# couple-pointing.net
KiCad netlist of a schematic drawn in EasyEDA Pro
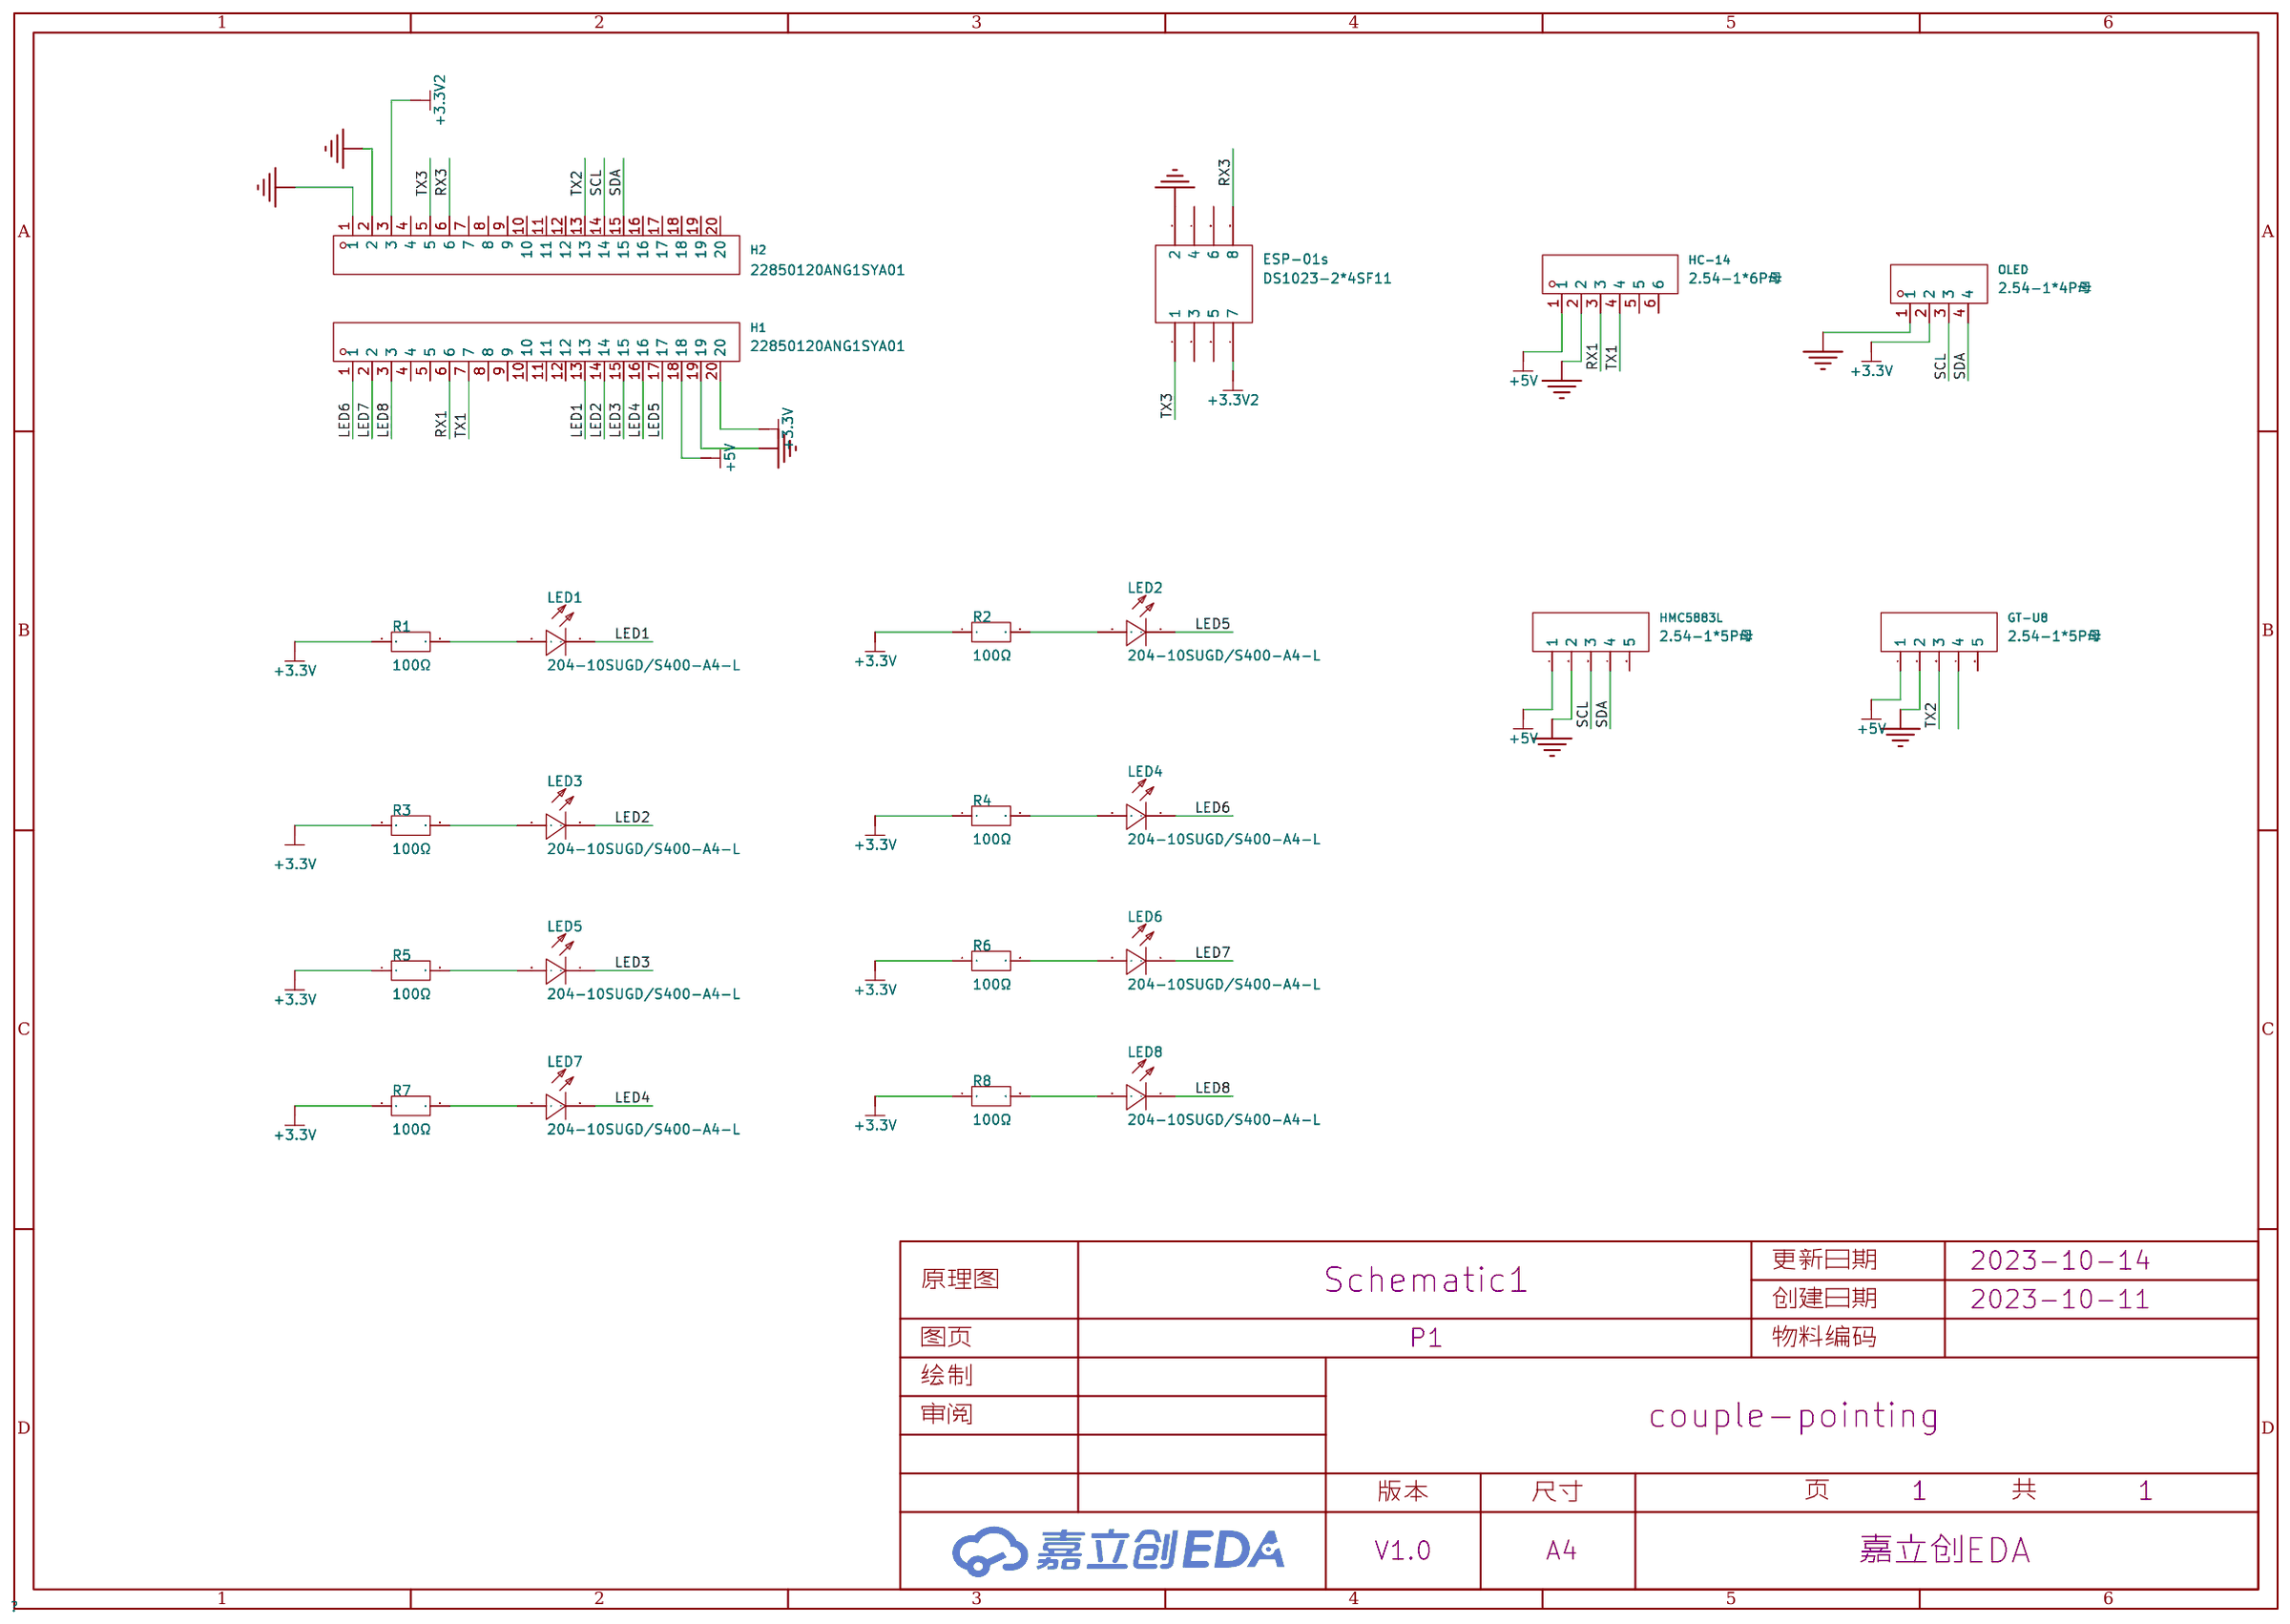
[diagram p0: schematic sheet]

(export (version "E")
  (design (tool "Eeschema 10.0.6"))
  (components
    (comp (ref "ESP-01s")
      (value "DS1023-2*4SF11")
      (footprint "easyedapro:HDR-TH_8P-P2.54-V-F-R2-C4-S2.54")
      (description "排数:双排;总孔位数:8P;间距:2.54mm;插孔结构:2x4P;行距:2.54mm;安装类型:直插;塑高:-;触头材质:-;触头镀层:-;")
      (fields (field (name "Manufacturer") "CONNFLY"))
      (libsource (lib "easyedapro") (part "DS1023-2*4SF11"))
    )
    (comp (ref "GT-U8")
      (value "2.54-1*5P母")
      (footprint "easyedapro:HDR-TH_5P-P2.54-V-F")
      (description "排数:单排;总孔位数:5P;间距:2.54mm;插孔结构:1x5P;行距:-;安装类型:直插;塑高:-;触头材质:-;触头镀层:-;")
      (fields (field (name "Manufacturer") "BOOMELE(博穆精密)"))
      (libsource (lib "easyedapro") (part "Header-Female-2.54_1x5"))
    )
    (comp (ref "H1")
      (value "22850120ANG1SYA01")
      (footprint "easyedapro:HDR-TH_20P-P2.54-V-F")
      (description "排数:单排;总孔位数:20P;间距:2.54mm;插孔结构:1x20P;行距:-;安装类型:直插;塑高:-;触头材质:黄铜;触头镀层:-;")
      (fields (field (name "Manufacturer") "JILN(锦凌)"))
      (libsource (lib "easyedapro") (part "22850120ANG1SYA01"))
    )
    (comp (ref "H2")
      (value "22850120ANG1SYA01")
      (footprint "easyedapro:HDR-TH_20P-P2.54-V-F")
      (description "排数:单排;总孔位数:20P;间距:2.54mm;插孔结构:1x20P;行距:-;安装类型:直插;塑高:-;触头材质:黄铜;触头镀层:-;")
      (fields (field (name "Manufacturer") "JILN(锦凌)"))
      (libsource (lib "easyedapro") (part "22850120ANG1SYA01"))
    )
    (comp (ref "HC-14")
      (value "2.54-1*6P母")
      (footprint "easyedapro:HDR-TH_6P-P2.54-V-F")
      (description "排数:单排;总孔位数:6P;间距:2.54mm;插孔结构:1x6P;行距:-;安装类型:直插;塑高:-;触头材质:-;触头镀层:-;")
      (fields (field (name "Manufacturer") "BOOMELE(博穆精密)"))
      (libsource (lib "easyedapro") (part "Header-Female-2.54_1x6"))
    )
    (comp (ref "HMC5883L")
      (value "2.54-1*5P母")
      (footprint "easyedapro:HDR-TH_5P-P2.54-V-F")
      (description "排数:单排;总孔位数:5P;间距:2.54mm;插孔结构:1x5P;行距:-;安装类型:直插;塑高:-;触头材质:-;触头镀层:-;")
      (fields (field (name "Manufacturer") "BOOMELE(博穆精密)"))
      (libsource (lib "easyedapro") (part "Header-Female-2.54_1x5"))
    )
    (comp (ref "LED1")
      (value "204-10SUGD/S400-A4-L")
      (footprint "easyedapro:LED-TH_BD3.9-P2.54-RD")
      (fields (field (name "Manufacturer") "EVERLIGHT(亿光)"))
      (libsource (lib "easyedapro") (part "204-10SUGD/S400-A4-L"))
    )
    (comp (ref "LED2")
      (value "204-10SUGD/S400-A4-L")
      (footprint "easyedapro:LED-TH_BD3.9-P2.54-RD")
      (fields (field (name "Manufacturer") "EVERLIGHT(亿光)"))
      (libsource (lib "easyedapro") (part "204-10SUGD/S400-A4-L"))
    )
    (comp (ref "LED3")
      (value "204-10SUGD/S400-A4-L")
      (footprint "easyedapro:LED-TH_BD3.9-P2.54-RD")
      (fields (field (name "Manufacturer") "EVERLIGHT(亿光)"))
      (libsource (lib "easyedapro") (part "204-10SUGD/S400-A4-L"))
    )
    (comp (ref "LED4")
      (value "204-10SUGD/S400-A4-L")
      (footprint "easyedapro:LED-TH_BD3.9-P2.54-RD")
      (fields (field (name "Manufacturer") "EVERLIGHT(亿光)"))
      (libsource (lib "easyedapro") (part "204-10SUGD/S400-A4-L"))
    )
    (comp (ref "LED5")
      (value "204-10SUGD/S400-A4-L")
      (footprint "easyedapro:LED-TH_BD3.9-P2.54-RD")
      (fields (field (name "Manufacturer") "EVERLIGHT(亿光)"))
      (libsource (lib "easyedapro") (part "204-10SUGD/S400-A4-L"))
    )
    (comp (ref "LED6")
      (value "204-10SUGD/S400-A4-L")
      (footprint "easyedapro:LED-TH_BD3.9-P2.54-RD")
      (fields (field (name "Manufacturer") "EVERLIGHT(亿光)"))
      (libsource (lib "easyedapro") (part "204-10SUGD/S400-A4-L"))
    )
    (comp (ref "LED7")
      (value "204-10SUGD/S400-A4-L")
      (footprint "easyedapro:LED-TH_BD3.9-P2.54-RD")
      (fields (field (name "Manufacturer") "EVERLIGHT(亿光)"))
      (libsource (lib "easyedapro") (part "204-10SUGD/S400-A4-L"))
    )
    (comp (ref "LED8")
      (value "204-10SUGD/S400-A4-L")
      (footprint "easyedapro:LED-TH_BD3.9-P2.54-RD")
      (fields (field (name "Manufacturer") "EVERLIGHT(亿光)"))
      (libsource (lib "easyedapro") (part "204-10SUGD/S400-A4-L"))
    )
    (comp (ref "OLED")
      (value "2.54-1*4P母")
      (footprint "easyedapro:HDR-TH_4P-P2.54-V-F")
      (fields (field (name "Manufacturer") "BOOMELE(博穆精密)"))
      (libsource (lib "easyedapro") (part "2.54-1*4P母"))
    )
    (comp (ref "R1")
      (value "100Ω")
      (footprint "easyedapro:RES-TH_BD2.4-L6.3-P10.30-D0.6")
      (description "电阻类型:金属膜电阻;阻值:100Ω;精度:±1%;功率:250mW;温度系数:±50ppm/°C;最大工作电压:250V;工作温度范围:-55°C~+125°C;")
      (fields
        (field (name "Manufacturer Part") "RN 1/4W 100R F T/B A1")
        (field (name "Manufacturer") "Tyohm(幸亚电阻)")
      )
      (libsource (lib "easyedapro") (part "RN 1/4W 100R F T/B A1"))
    )
    (comp (ref "R2")
      (value "100Ω")
      (footprint "easyedapro:RES-TH_BD2.4-L6.3-P10.30-D0.6")
      (description "电阻类型:金属膜电阻;阻值:100Ω;精度:±1%;功率:250mW;温度系数:±50ppm/°C;最大工作电压:250V;工作温度范围:-55°C~+125°C;")
      (fields
        (field (name "Manufacturer Part") "RN 1/4W 100R F T/B A1")
        (field (name "Manufacturer") "Tyohm(幸亚电阻)")
      )
      (libsource (lib "easyedapro") (part "RN 1/4W 100R F T/B A1"))
    )
    (comp (ref "R3")
      (value "100Ω")
      (footprint "easyedapro:RES-TH_BD2.4-L6.3-P10.30-D0.6")
      (description "电阻类型:金属膜电阻;阻值:100Ω;精度:±1%;功率:250mW;温度系数:±50ppm/°C;最大工作电压:250V;工作温度范围:-55°C~+125°C;")
      (fields
        (field (name "Manufacturer Part") "RN 1/4W 100R F T/B A1")
        (field (name "Manufacturer") "Tyohm(幸亚电阻)")
      )
      (libsource (lib "easyedapro") (part "RN 1/4W 100R F T/B A1"))
    )
    (comp (ref "R4")
      (value "100Ω")
      (footprint "easyedapro:RES-TH_BD2.4-L6.3-P10.30-D0.6")
      (description "电阻类型:金属膜电阻;阻值:100Ω;精度:±1%;功率:250mW;温度系数:±50ppm/°C;最大工作电压:250V;工作温度范围:-55°C~+125°C;")
      (fields
        (field (name "Manufacturer Part") "RN 1/4W 100R F T/B A1")
        (field (name "Manufacturer") "Tyohm(幸亚电阻)")
      )
      (libsource (lib "easyedapro") (part "RN 1/4W 100R F T/B A1"))
    )
    (comp (ref "R5")
      (value "100Ω")
      (footprint "easyedapro:RES-TH_BD2.4-L6.3-P10.30-D0.6")
      (description "电阻类型:金属膜电阻;阻值:100Ω;精度:±1%;功率:250mW;温度系数:±50ppm/°C;最大工作电压:250V;工作温度范围:-55°C~+125°C;")
      (fields
        (field (name "Manufacturer Part") "RN 1/4W 100R F T/B A1")
        (field (name "Manufacturer") "Tyohm(幸亚电阻)")
      )
      (libsource (lib "easyedapro") (part "RN 1/4W 100R F T/B A1"))
    )
    (comp (ref "R6")
      (value "100Ω")
      (footprint "easyedapro:RES-TH_BD2.4-L6.3-P10.30-D0.6")
      (description "电阻类型:金属膜电阻;阻值:100Ω;精度:±1%;功率:250mW;温度系数:±50ppm/°C;最大工作电压:250V;工作温度范围:-55°C~+125°C;")
      (fields
        (field (name "Manufacturer Part") "RN 1/4W 100R F T/B A1")
        (field (name "Manufacturer") "Tyohm(幸亚电阻)")
      )
      (libsource (lib "easyedapro") (part "RN 1/4W 100R F T/B A1"))
    )
    (comp (ref "R7")
      (value "100Ω")
      (footprint "easyedapro:RES-TH_BD2.4-L6.3-P10.30-D0.6")
      (description "电阻类型:金属膜电阻;阻值:100Ω;精度:±1%;功率:250mW;温度系数:±50ppm/°C;最大工作电压:250V;工作温度范围:-55°C~+125°C;")
      (fields
        (field (name "Manufacturer Part") "RN 1/4W 100R F T/B A1")
        (field (name "Manufacturer") "Tyohm(幸亚电阻)")
      )
      (libsource (lib "easyedapro") (part "RN 1/4W 100R F T/B A1"))
    )
    (comp (ref "R8")
      (value "100Ω")
      (footprint "easyedapro:RES-TH_BD2.4-L6.3-P10.30-D0.6")
      (description "电阻类型:金属膜电阻;阻值:100Ω;精度:±1%;功率:250mW;温度系数:±50ppm/°C;最大工作电压:250V;工作温度范围:-55°C~+125°C;")
      (fields
        (field (name "Manufacturer Part") "RN 1/4W 100R F T/B A1")
        (field (name "Manufacturer") "Tyohm(幸亚电阻)")
      )
      (libsource (lib "easyedapro") (part "RN 1/4W 100R F T/B A1"))
    )
  )
  (nets
    (net (code "1") (name "+3.3V") (class "Default")
      (node (ref "H1") (pin "20") (pinfunction "20_20") (pintype "input"))
      (node (ref "OLED") (pin "2") (pinfunction "2_2") (pintype "input"))
      (node (ref "R1") (pin "1") (pinfunction "1_1") (pintype "input"))
      (node (ref "R2") (pin "1") (pinfunction "1_1") (pintype "input"))
      (node (ref "R3") (pin "1") (pinfunction "1_1") (pintype "input"))
      (node (ref "R4") (pin "1") (pinfunction "1_1") (pintype "input"))
      (node (ref "R5") (pin "1") (pinfunction "1_1") (pintype "input"))
      (node (ref "R6") (pin "1") (pinfunction "1_1") (pintype "input"))
      (node (ref "R7") (pin "1") (pinfunction "1_1") (pintype "input"))
      (node (ref "R8") (pin "1") (pinfunction "1_1") (pintype "input"))
    )
    (net (code "2") (name "+3.3V2") (class "Default")
      (node (ref "ESP-01s") (pin "7") (pinfunction "7_7") (pintype "input"))
      (node (ref "H2") (pin "3") (pinfunction "3_3") (pintype "input"))
    )
    (net (code "3") (name "+5V") (class "Default")
      (node (ref "GT-U8") (pin "1") (pinfunction "1_1") (pintype "input"))
      (node (ref "H1") (pin "18") (pinfunction "18_18") (pintype "input"))
      (node (ref "HC-14") (pin "1") (pinfunction "1_1") (pintype "input"))
      (node (ref "HMC5883L") (pin "1") (pinfunction "1_1") (pintype "input"))
    )
    (net (code "4") (name "/LED1") (class "Default")
      (node (ref "H1") (pin "13") (pinfunction "13_13") (pintype "input"))
      (node (ref "LED1") (pin "1") (pinfunction "-_1") (pintype "input"))
    )
    (net (code "5") (name "/LED2") (class "Default")
      (node (ref "H1") (pin "14") (pinfunction "14_14") (pintype "input"))
      (node (ref "LED3") (pin "1") (pinfunction "-_1") (pintype "input"))
    )
    (net (code "6") (name "/LED3") (class "Default")
      (node (ref "H1") (pin "15") (pinfunction "15_15") (pintype "input"))
      (node (ref "LED5") (pin "1") (pinfunction "-_1") (pintype "input"))
    )
    (net (code "7") (name "/LED4") (class "Default")
      (node (ref "H1") (pin "16") (pinfunction "16_16") (pintype "input"))
      (node (ref "LED7") (pin "1") (pinfunction "-_1") (pintype "input"))
    )
    (net (code "8") (name "/LED5") (class "Default")
      (node (ref "H1") (pin "17") (pinfunction "17_17") (pintype "input"))
      (node (ref "LED2") (pin "1") (pinfunction "-_1") (pintype "input"))
    )
    (net (code "9") (name "/LED6") (class "Default")
      (node (ref "H1") (pin "1") (pinfunction "1_1") (pintype "input"))
      (node (ref "LED4") (pin "1") (pinfunction "-_1") (pintype "input"))
    )
    (net (code "10") (name "/LED7") (class "Default")
      (node (ref "H1") (pin "2") (pinfunction "2_2") (pintype "input"))
      (node (ref "LED6") (pin "1") (pinfunction "-_1") (pintype "input"))
    )
    (net (code "11") (name "/LED8") (class "Default")
      (node (ref "H1") (pin "3") (pinfunction "3_3") (pintype "input"))
      (node (ref "LED8") (pin "1") (pinfunction "-_1") (pintype "input"))
    )
    (net (code "12") (name "/RX1") (class "Default")
      (node (ref "H1") (pin "6") (pinfunction "6_6") (pintype "input"))
      (node (ref "HC-14") (pin "3") (pinfunction "3_3") (pintype "input"))
    )
    (net (code "13") (name "/RX3") (class "Default")
      (node (ref "ESP-01s") (pin "8") (pinfunction "8_8") (pintype "input"))
      (node (ref "H2") (pin "6") (pinfunction "6_6") (pintype "input"))
    )
    (net (code "14") (name "/SCL") (class "Default")
      (node (ref "H2") (pin "14") (pinfunction "14_14") (pintype "input"))
      (node (ref "HMC5883L") (pin "3") (pinfunction "3_3") (pintype "input"))
      (node (ref "OLED") (pin "3") (pinfunction "3_3") (pintype "input"))
    )
    (net (code "15") (name "/SDA") (class "Default")
      (node (ref "H2") (pin "15") (pinfunction "15_15") (pintype "input"))
      (node (ref "HMC5883L") (pin "4") (pinfunction "4_4") (pintype "input"))
      (node (ref "OLED") (pin "4") (pinfunction "4_4") (pintype "input"))
    )
    (net (code "16") (name "/TX1") (class "Default")
      (node (ref "H1") (pin "7") (pinfunction "7_7") (pintype "input"))
      (node (ref "HC-14") (pin "4") (pinfunction "4_4") (pintype "input"))
    )
    (net (code "17") (name "/TX2") (class "Default")
      (node (ref "GT-U8") (pin "3") (pinfunction "3_3") (pintype "input"))
      (node (ref "H2") (pin "13") (pinfunction "13_13") (pintype "input"))
    )
    (net (code "18") (name "/TX3") (class "Default")
      (node (ref "ESP-01s") (pin "1") (pinfunction "1_1") (pintype "input"))
      (node (ref "H2") (pin "5") (pinfunction "5_5") (pintype "input"))
    )
    (net (code "19") (name "GND") (class "Default")
      (node (ref "ESP-01s") (pin "2") (pinfunction "2_2") (pintype "input"))
      (node (ref "GT-U8") (pin "2") (pinfunction "2_2") (pintype "input"))
      (node (ref "H1") (pin "19") (pinfunction "19_19") (pintype "input"))
      (node (ref "H2") (pin "1") (pinfunction "1_1") (pintype "input"))
      (node (ref "H2") (pin "2") (pinfunction "2_2") (pintype "input"))
      (node (ref "HC-14") (pin "2") (pinfunction "2_2") (pintype "input"))
      (node (ref "HMC5883L") (pin "2") (pinfunction "2_2") (pintype "input"))
      (node (ref "OLED") (pin "1") (pinfunction "1_1") (pintype "input"))
    )
    (net (code "20") (name "Net-(LED1-+)") (class "Default")
      (node (ref "LED1") (pin "2") (pinfunction "+_2") (pintype "input"))
      (node (ref "R1") (pin "2") (pinfunction "2_2") (pintype "input"))
    )
    (net (code "21") (name "Net-(LED2-+)") (class "Default")
      (node (ref "LED2") (pin "2") (pinfunction "+_2") (pintype "input"))
      (node (ref "R2") (pin "2") (pinfunction "2_2") (pintype "input"))
    )
    (net (code "22") (name "Net-(LED3-+)") (class "Default")
      (node (ref "LED3") (pin "2") (pinfunction "+_2") (pintype "input"))
      (node (ref "R3") (pin "2") (pinfunction "2_2") (pintype "input"))
    )
    (net (code "23") (name "Net-(LED4-+)") (class "Default")
      (node (ref "LED4") (pin "2") (pinfunction "+_2") (pintype "input"))
      (node (ref "R4") (pin "2") (pinfunction "2_2") (pintype "input"))
    )
    (net (code "24") (name "Net-(LED5-+)") (class "Default")
      (node (ref "LED5") (pin "2") (pinfunction "+_2") (pintype "input"))
      (node (ref "R5") (pin "2") (pinfunction "2_2") (pintype "input"))
    )
    (net (code "25") (name "Net-(LED6-+)") (class "Default")
      (node (ref "LED6") (pin "2") (pinfunction "+_2") (pintype "input"))
      (node (ref "R6") (pin "2") (pinfunction "2_2") (pintype "input"))
    )
    (net (code "26") (name "Net-(LED7-+)") (class "Default")
      (node (ref "LED7") (pin "2") (pinfunction "+_2") (pintype "input"))
      (node (ref "R7") (pin "2") (pinfunction "2_2") (pintype "input"))
    )
    (net (code "27") (name "Net-(LED8-+)") (class "Default")
      (node (ref "LED8") (pin "2") (pinfunction "+_2") (pintype "input"))
      (node (ref "R8") (pin "2") (pinfunction "2_2") (pintype "input"))
    )
    (net (code "28") (name "unconnected-(ESP-01s-Pad3)") (class "Default")
      (node (ref "ESP-01s") (pin "3") (pinfunction "3_3") (pintype "input"))
    )
    (net (code "29") (name "unconnected-(ESP-01s-Pad4)") (class "Default")
      (node (ref "ESP-01s") (pin "4") (pinfunction "4_4") (pintype "input"))
    )
    (net (code "30") (name "unconnected-(ESP-01s-Pad5)") (class "Default")
      (node (ref "ESP-01s") (pin "5") (pinfunction "5_5") (pintype "input"))
    )
    (net (code "31") (name "unconnected-(ESP-01s-Pad6)") (class "Default")
      (node (ref "ESP-01s") (pin "6") (pinfunction "6_6") (pintype "input"))
    )
    (net (code "32") (name "unconnected-(GT-U8-Pad4)") (class "Default")
      (node (ref "GT-U8") (pin "4") (pinfunction "4_4") (pintype "input"))
    )
    (net (code "33") (name "unconnected-(GT-U8-Pad5)") (class "Default")
      (node (ref "GT-U8") (pin "5") (pinfunction "5_5") (pintype "input"))
    )
    (net (code "34") (name "unconnected-(H1-Pad4)") (class "Default")
      (node (ref "H1") (pin "4") (pinfunction "4_4") (pintype "input"))
    )
    (net (code "35") (name "unconnected-(H1-Pad5)") (class "Default")
      (node (ref "H1") (pin "5") (pinfunction "5_5") (pintype "input"))
    )
    (net (code "36") (name "unconnected-(H1-Pad8)") (class "Default")
      (node (ref "H1") (pin "8") (pinfunction "8_8") (pintype "input"))
    )
    (net (code "37") (name "unconnected-(H1-Pad9)") (class "Default")
      (node (ref "H1") (pin "9") (pinfunction "9_9") (pintype "input"))
    )
    (net (code "38") (name "unconnected-(H1-Pad10)") (class "Default")
      (node (ref "H1") (pin "10") (pinfunction "10_10") (pintype "input"))
    )
    (net (code "39") (name "unconnected-(H1-Pad11)") (class "Default")
      (node (ref "H1") (pin "11") (pinfunction "11_11") (pintype "input"))
    )
    (net (code "40") (name "unconnected-(H1-Pad12)") (class "Default")
      (node (ref "H1") (pin "12") (pinfunction "12_12") (pintype "input"))
    )
    (net (code "41") (name "unconnected-(H2-Pad4)") (class "Default")
      (node (ref "H2") (pin "4") (pinfunction "4_4") (pintype "input"))
    )
    (net (code "42") (name "unconnected-(H2-Pad7)") (class "Default")
      (node (ref "H2") (pin "7") (pinfunction "7_7") (pintype "input"))
    )
    (net (code "43") (name "unconnected-(H2-Pad8)") (class "Default")
      (node (ref "H2") (pin "8") (pinfunction "8_8") (pintype "input"))
    )
    (net (code "44") (name "unconnected-(H2-Pad9)") (class "Default")
      (node (ref "H2") (pin "9") (pinfunction "9_9") (pintype "input"))
    )
    (net (code "45") (name "unconnected-(H2-Pad10)") (class "Default")
      (node (ref "H2") (pin "10") (pinfunction "10_10") (pintype "input"))
    )
    (net (code "46") (name "unconnected-(H2-Pad11)") (class "Default")
      (node (ref "H2") (pin "11") (pinfunction "11_11") (pintype "input"))
    )
    (net (code "47") (name "unconnected-(H2-Pad12)") (class "Default")
      (node (ref "H2") (pin "12") (pinfunction "12_12") (pintype "input"))
    )
    (net (code "48") (name "unconnected-(H2-Pad16)") (class "Default")
      (node (ref "H2") (pin "16") (pinfunction "16_16") (pintype "input"))
    )
    (net (code "49") (name "unconnected-(H2-Pad17)") (class "Default")
      (node (ref "H2") (pin "17") (pinfunction "17_17") (pintype "input"))
    )
    (net (code "50") (name "unconnected-(H2-Pad18)") (class "Default")
      (node (ref "H2") (pin "18") (pinfunction "18_18") (pintype "input"))
    )
    (net (code "51") (name "unconnected-(H2-Pad19)") (class "Default")
      (node (ref "H2") (pin "19") (pinfunction "19_19") (pintype "input"))
    )
    (net (code "52") (name "unconnected-(H2-Pad20)") (class "Default")
      (node (ref "H2") (pin "20") (pinfunction "20_20") (pintype "input"))
    )
    (net (code "53") (name "unconnected-(HC-14-Pad5)") (class "Default")
      (node (ref "HC-14") (pin "5") (pinfunction "5_5") (pintype "input"))
    )
    (net (code "54") (name "unconnected-(HC-14-Pad6)") (class "Default")
      (node (ref "HC-14") (pin "6") (pinfunction "6_6") (pintype "input"))
    )
    (net (code "55") (name "unconnected-(HMC5883L-Pad5)") (class "Default")
      (node (ref "HMC5883L") (pin "5") (pinfunction "5_5") (pintype "input"))
    )
  )
)
